# IQDemod.net
KiCad netlist of a schematic drawn in Altium Designer
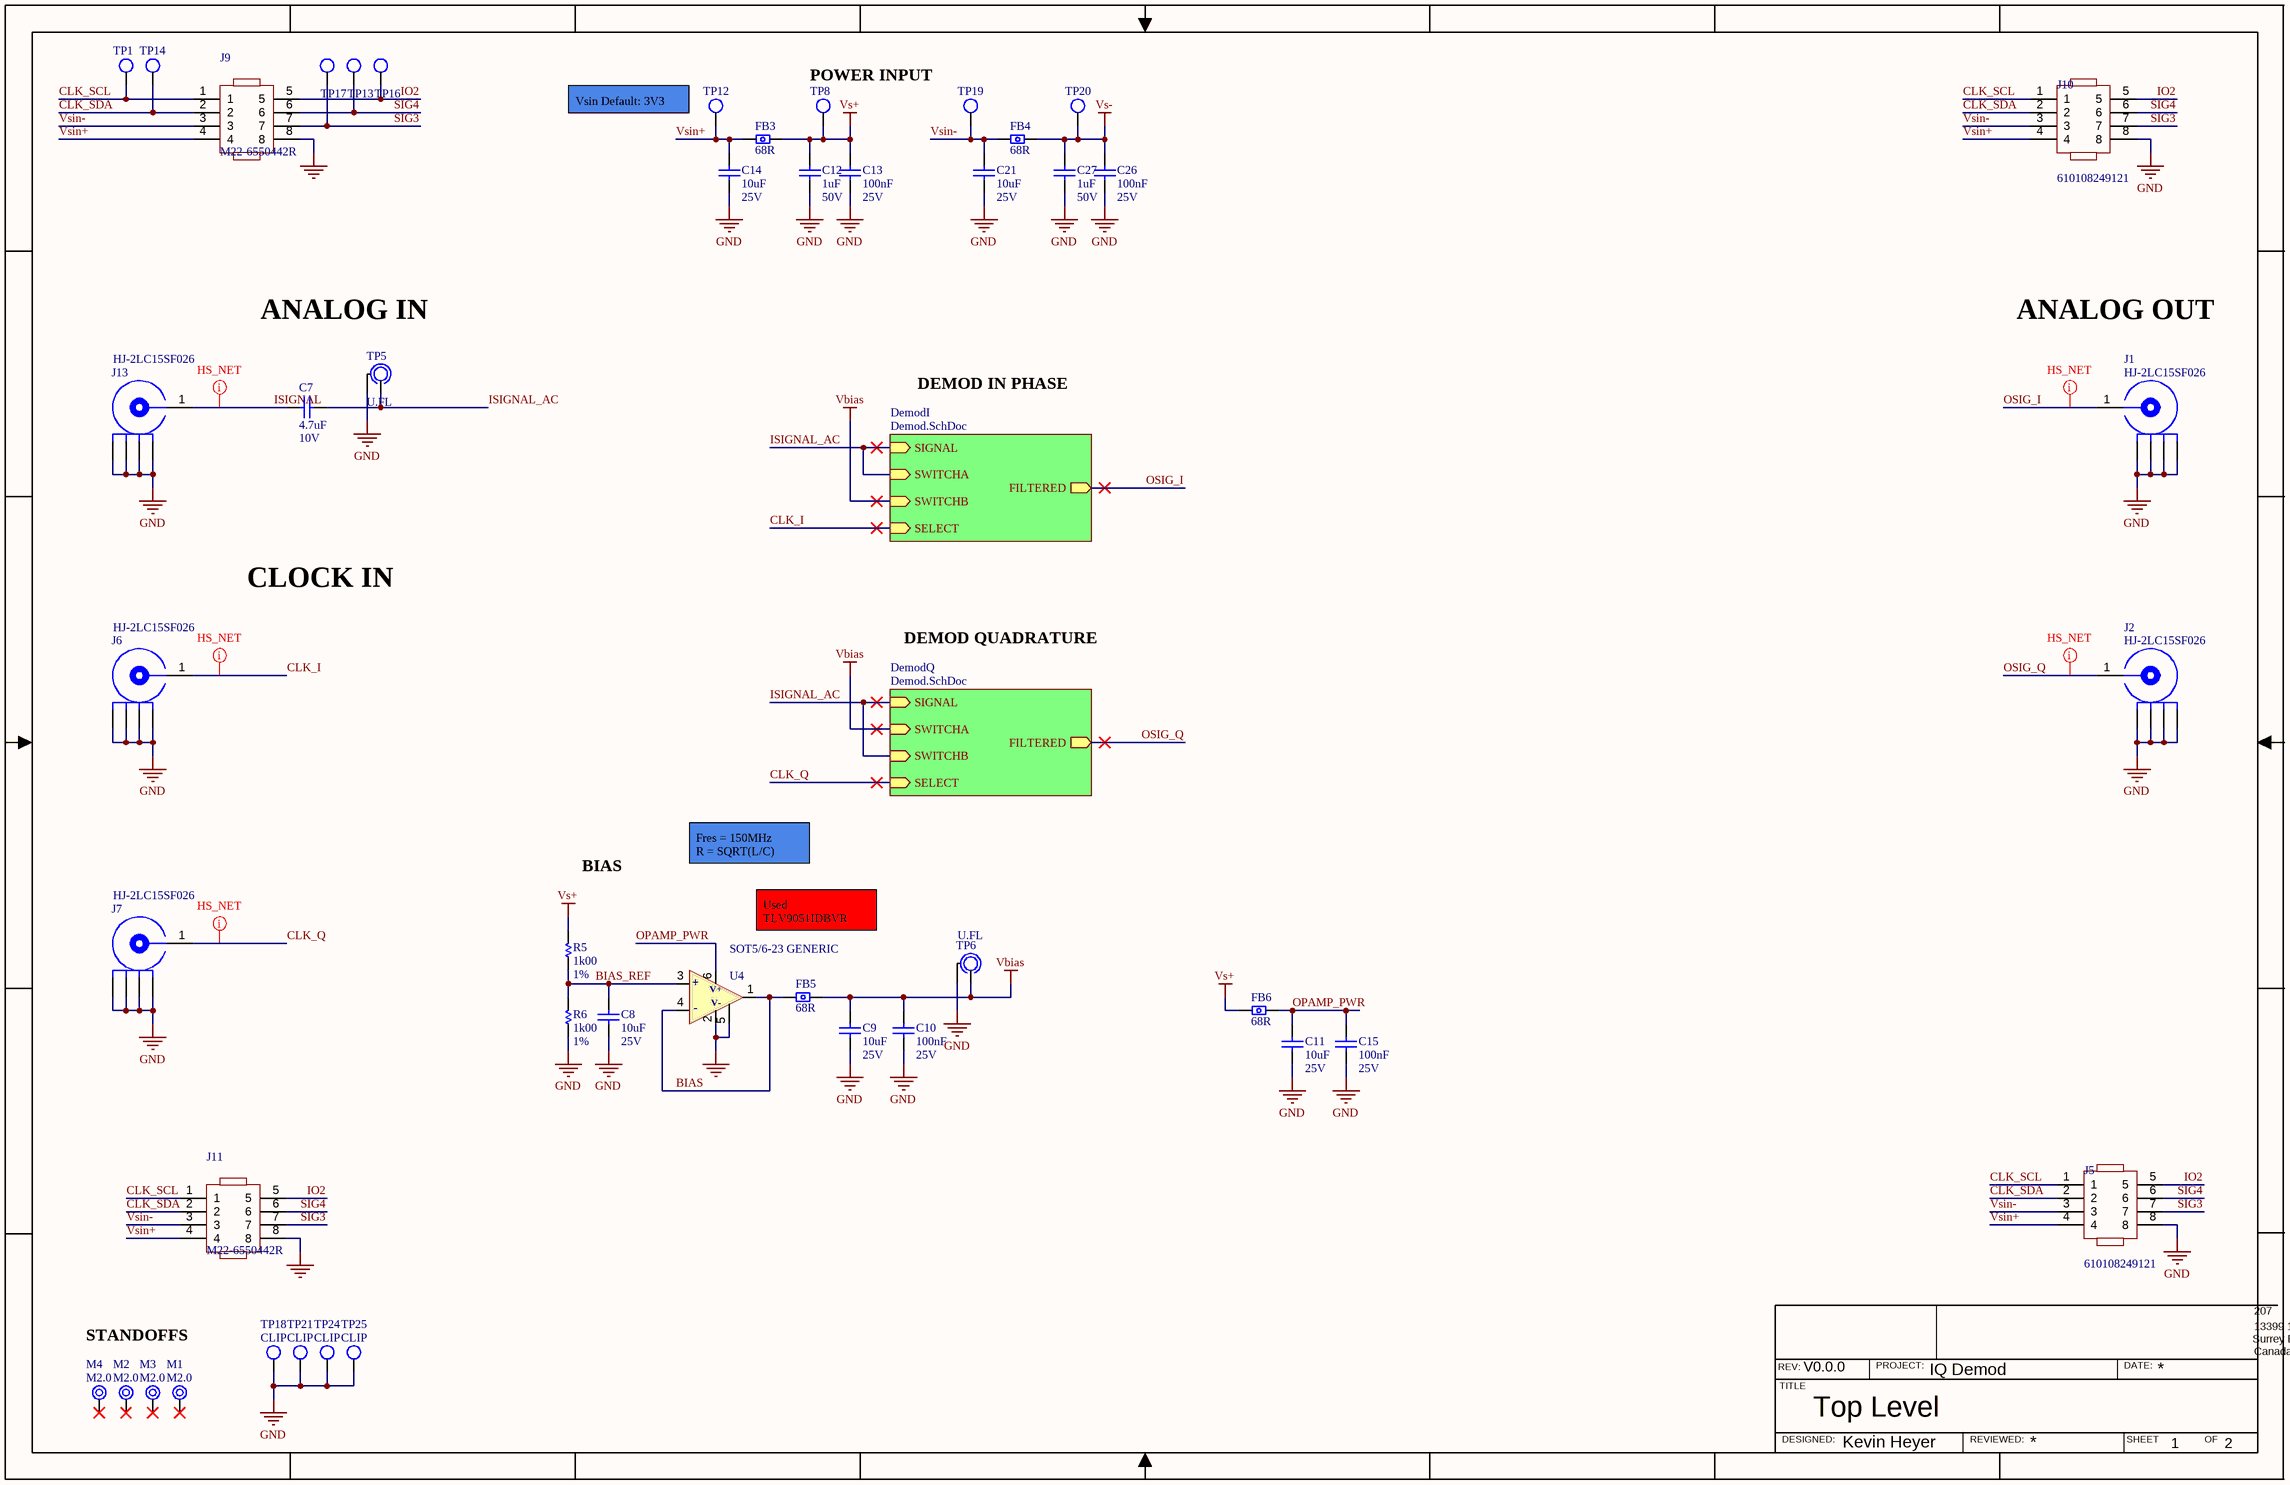
[diagram p0: IQDemod.SchDoc]

(export (version "E")
  (design (tool "Eeschema 10.0.6"))
  (components
    (comp (ref "C7")
      (value "4.7uF")
      (footprint "C0402")
      (description "0402 10 V 4.7 uF ±20% Tolerance X5R Multilayer Ceramic Chip Capacitor")
      (fields
        (field (name "MANUFACTURER") "Murata")
        (field (name "MANUFACTURER PART NUMBER") "GRM155R61A475MEAAD")
        (field (name "VOLTAGE RATING") "10V")
      )
      (libsource (lib "Symbols") (part "CAP CER 4.7uF 10V X5R 0402"))
    )
    (comp (ref "C8")
      (value "10uF")
      (footprint "c0805")
      (description "Cap Ceramic 10uF 25V X5R 10% SMD 0805 85°C Embossed T/R")
      (fields
        (field (name "MANUFACTURER") "Samsung")
        (field (name "MANUFACTURER PART NUMBER") "CL21A106KAYNNNE")
        (field (name "VOLTAGE RATING") "25V")
      )
      (libsource (lib "OPAMP_DEV_SOT5_6-23") (part "CAP CER 10uF 25V X5R 0805"))
    )
    (comp (ref "C9")
      (value "10uF")
      (footprint "c0805")
      (description "Cap Ceramic 10uF 25V X5R 10% SMD 0805 85°C Embossed T/R")
      (fields
        (field (name "MANUFACTURER") "Samsung")
        (field (name "MANUFACTURER PART NUMBER") "CL21A106KAYNNNE")
        (field (name "VOLTAGE RATING") "25V")
      )
      (libsource (lib "OPAMP_DEV_SOT5_6-23") (part "CAP CER 10uF 25V X5R 0805"))
    )
    (comp (ref "C10")
      (value "100nF")
      (footprint "C0402")
      (description "Cap Ceramic 0.1uF 25V X5R 10% Pad SMD 0402 85°C T/R / Multi Layer Ceramic Capacitor (MLCC)")
      (fields
        (field (name "MANUFACTURER") "Samsung")
        (field (name "MANUFACTURER PART NUMBER") "CL05A104KA5NNNC")
        (field (name "VOLTAGE RATING") "25V")
      )
      (libsource (lib "OPAMP_DEV_SOT5_6-23") (part "CAP CER 100nF 25V X5R 0402"))
    )
    (comp (ref "C11")
      (value "10uF")
      (footprint "c0805")
      (description "Cap Ceramic 10uF 25V X5R 10% SMD 0805 85°C Embossed T/R")
      (fields
        (field (name "MANUFACTURER") "Samsung")
        (field (name "MANUFACTURER PART NUMBER") "CL21A106KAYNNNE")
        (field (name "VOLTAGE RATING") "25V")
      )
      (libsource (lib "OPAMP_DEV_SOT5_6-23") (part "CAP CER 10uF 25V X5R 0805"))
    )
    (comp (ref "C12")
      (value "1uF")
      (footprint "c0603")
      (description "Multilayer Ceramic Capacitors (High dielectric type), 50V, 1 uF, ± 10 %, 0603, X5R, RoHS")
      (fields
        (field (name "MANUFACTURER") "Taiyo Yuden")
        (field (name "MANUFACTURER PART NUMBER") "UMK107BJ105KA-T")
        (field (name "VOLTAGE RATING") "50V")
      )
      (libsource (lib "OPAMP_DEV_SOT5_6-23") (part "CAP CER 1uF 50V X5R 0603"))
    )
    (comp (ref "C13")
      (value "100nF")
      (footprint "C0402")
      (description "Cap Ceramic 0.1uF 25V X5R 10% Pad SMD 0402 85°C T/R / Multi Layer Ceramic Capacitor (MLCC)")
      (fields
        (field (name "MANUFACTURER") "Samsung")
        (field (name "MANUFACTURER PART NUMBER") "CL05A104KA5NNNC")
        (field (name "VOLTAGE RATING") "25V")
      )
      (libsource (lib "OPAMP_DEV_SOT5_6-23") (part "CAP CER 100nF 25V X5R 0402"))
    )
    (comp (ref "C14")
      (value "10uF")
      (footprint "c0805")
      (description "Cap Ceramic 10uF 25V X5R 10% SMD 0805 85°C Embossed T/R")
      (fields
        (field (name "MANUFACTURER") "Samsung")
        (field (name "MANUFACTURER PART NUMBER") "CL21A106KAYNNNE")
        (field (name "VOLTAGE RATING") "25V")
      )
      (libsource (lib "OPAMP_DEV_SOT5_6-23") (part "CAP CER 10uF 25V X5R 0805"))
    )
    (comp (ref "C15")
      (value "100nF")
      (footprint "C0402")
      (description "Cap Ceramic 0.1uF 25V X5R 10% Pad SMD 0402 85°C T/R / Multi Layer Ceramic Capacitor (MLCC)")
      (fields
        (field (name "MANUFACTURER") "Samsung")
        (field (name "MANUFACTURER PART NUMBER") "CL05A104KA5NNNC")
        (field (name "VOLTAGE RATING") "25V")
      )
      (libsource (lib "OPAMP_DEV_SOT5_6-23") (part "CAP CER 100nF 25V X5R 0402"))
    )
    (comp (ref "C21")
      (value "10uF")
      (footprint "c0805")
      (description "Cap Ceramic 10uF 25V X5R 10% SMD 0805 85°C Embossed T/R")
      (fields
        (field (name "MANUFACTURER") "Samsung")
        (field (name "MANUFACTURER PART NUMBER") "CL21A106KAYNNNE")
        (field (name "VOLTAGE RATING") "25V")
      )
      (libsource (lib "OPAMP_DEV_SOT5_6-23") (part "CAP CER 10uF 25V X5R 0805"))
    )
    (comp (ref "C26")
      (value "100nF")
      (footprint "C0402")
      (description "Cap Ceramic 0.1uF 25V X5R 10% Pad SMD 0402 85°C T/R / Multi Layer Ceramic Capacitor (MLCC)")
      (fields
        (field (name "MANUFACTURER") "Samsung")
        (field (name "MANUFACTURER PART NUMBER") "CL05A104KA5NNNC")
        (field (name "VOLTAGE RATING") "25V")
      )
      (libsource (lib "OPAMP_DEV_SOT5_6-23") (part "CAP CER 100nF 25V X5R 0402"))
    )
    (comp (ref "C27")
      (value "1uF")
      (footprint "c0603")
      (description "Multilayer Ceramic Capacitors (High dielectric type), 50V, 1 uF, ± 10 %, 0603, X5R, RoHS")
      (fields
        (field (name "MANUFACTURER") "Taiyo Yuden")
        (field (name "MANUFACTURER PART NUMBER") "UMK107BJ105KA-T")
        (field (name "VOLTAGE RATING") "50V")
      )
      (libsource (lib "OPAMP_DEV_SOT5_6-23") (part "CAP CER 1uF 50V X5R 0603"))
    )
    (comp (ref "FB3")
      (value "68R")
      (footprint "FB0402")
      (description "Ferrite Beads Multi-Layer 68Ohm 25% 100MHz 400mA 310mOhm DCR 0402 T/R")
      (fields
        (field (name "MANUFACTURER") "Taiyo Yuden")
        (field (name "MANUFACTURER PART NUMBER") "BK1005LL680-T")
      )
      (libsource (lib "MCU") (part "FB 68R 400mA 310mR 0402"))
    )
    (comp (ref "FB4")
      (value "68R")
      (footprint "FB0402")
      (description "Ferrite Beads Multi-Layer 68Ohm 25% 100MHz 400mA 310mOhm DCR 0402 T/R")
      (fields
        (field (name "MANUFACTURER") "Taiyo Yuden")
        (field (name "MANUFACTURER PART NUMBER") "BK1005LL680-T")
      )
      (libsource (lib "MCU") (part "FB 68R 400mA 310mR 0402"))
    )
    (comp (ref "FB5")
      (value "68R")
      (footprint "FB0402")
      (description "Ferrite Beads Multi-Layer 68Ohm 25% 100MHz 400mA 310mOhm DCR 0402 T/R")
      (fields
        (field (name "MANUFACTURER") "Taiyo Yuden")
        (field (name "MANUFACTURER PART NUMBER") "BK1005LL680-T")
      )
      (libsource (lib "MCU") (part "FB 68R 400mA 310mR 0402"))
    )
    (comp (ref "FB6")
      (value "68R")
      (footprint "FB0402")
      (description "Ferrite Beads Multi-Layer 68Ohm 25% 100MHz 400mA 310mOhm DCR 0402 T/R")
      (fields
        (field (name "MANUFACTURER") "Taiyo Yuden")
        (field (name "MANUFACTURER PART NUMBER") "BK1005LL680-T")
      )
      (libsource (lib "MCU") (part "FB 68R 400mA 310mR 0402"))
    )
    (comp (ref "J1")
      (value "HJ-2LC15SF026")
      (footprint "SMA TH BORE")
      (libsource (lib "") (part "CON SMA BORE TH HJ-SMA058_1"))
    )
    (comp (ref "J2")
      (value "HJ-2LC15SF026")
      (footprint "SMA TH BORE")
      (libsource (lib "") (part "CON SMA BORE TH HJ-SMA058_1"))
    )
    (comp (ref "J5")
      (value "610108249121")
      (footprint "CONN HDR 08 MALE RA 2ROW - duplicate")
      (description "SMT Angled Pin Header WR-PHD, Pitch 2.54 mm, Dual Row, 8 pins")
      (fields (field (name "MANUFACTURER") "Wurth Electronics"))
      (libsource (lib "Symbols") (part "CONN HDR 08 MALE RA 2 ROW"))
    )
    (comp (ref "J6")
      (value "HJ-2LC15SF026")
      (footprint "SMA TH BORE")
      (libsource (lib "Symbols") (part "CON SMA BORE TH HJ-SMA058"))
    )
    (comp (ref "J7")
      (value "HJ-2LC15SF026")
      (footprint "SMA TH BORE")
      (libsource (lib "Symbols") (part "CON SMA BORE TH HJ-SMA058"))
    )
    (comp (ref "J9")
      (value "M22-6550442R")
      (footprint "CONN HDR 08 FEMALE RA 2ROW")
      (description "Conn Socket Strip RCP 8 POS 2mm Solder RA SMD T/R")
      (fields (field (name "MANUFACTURER") "Harwin"))
      (libsource (lib "Symbols") (part "CONN HDR 08 FEMALE RA 2 ROW"))
    )
    (comp (ref "J10")
      (value "610108249121")
      (footprint "CONN HDR 08 MALE RA 2ROW - duplicate")
      (description "SMT Angled Pin Header WR-PHD, Pitch 2.54 mm, Dual Row, 8 pins")
      (fields (field (name "MANUFACTURER") "Wurth Electronics"))
      (libsource (lib "Symbols") (part "CONN HDR 08 MALE RA 2 ROW"))
    )
    (comp (ref "J11")
      (value "M22-6550442R")
      (footprint "CONN HDR 08 FEMALE RA 2ROW")
      (description "Conn Socket Strip RCP 8 POS 2mm Solder RA SMD T/R")
      (fields (field (name "MANUFACTURER") "Harwin"))
      (libsource (lib "Symbols") (part "CONN HDR 08 FEMALE RA 2 ROW"))
    )
    (comp (ref "J13")
      (value "HJ-2LC15SF026")
      (footprint "SMA TH BORE")
      (libsource (lib "Symbols") (part "CON SMA BORE TH HJ-SMA058"))
    )
    (comp (ref "M1")
      (value "M2.0")
      (footprint "MECH M2.0 UNPLATED")
      (libsource (lib "OPAMP_DEV_SOT5_6-23") (part "MECH M2.0 UNPLATED"))
    )
    (comp (ref "M2")
      (value "M2.0")
      (footprint "MECH M2.0 UNPLATED")
      (libsource (lib "OPAMP_DEV_SOT5_6-23") (part "MECH M2.0 UNPLATED"))
    )
    (comp (ref "M3")
      (value "M2.0")
      (footprint "MECH M2.0 UNPLATED")
      (libsource (lib "OPAMP_DEV_SOT5_6-23") (part "MECH M2.0 UNPLATED"))
    )
    (comp (ref "M4")
      (value "M2.0")
      (footprint "MECH M2.0 UNPLATED")
      (libsource (lib "OPAMP_DEV_SOT5_6-23") (part "MECH M2.0 UNPLATED"))
    )
    (comp (ref "R5")
      (value "1k00")
      (footprint "R0402")
      (description "1 kOhms ±1% 0.063W, 1/16W Chip Resistor 0402 (1005 Metric) Moisture Resistant Thick Film")
      (fields
        (field (name "MANUFACTURER") "Yageo")
        (field (name "MANUFACTURER PART NUMBER") "RC0402FR-071KL")
        (field (name "TOLERANCE") "1%")
      )
      (libsource (lib "Symbols") (part "RES 1k00 63mW 0402"))
    )
    (comp (ref "R6")
      (value "1k00")
      (footprint "R0402")
      (description "1 kOhms ±1% 0.063W, 1/16W Chip Resistor 0402 (1005 Metric) Moisture Resistant Thick Film")
      (fields
        (field (name "MANUFACTURER") "Yageo")
        (field (name "MANUFACTURER PART NUMBER") "RC0402FR-071KL")
        (field (name "TOLERANCE") "1%")
      )
      (libsource (lib "Symbols") (part "RES 1k00 63mW 0402"))
    )
    (comp (ref "TP1")
      (value "1mm")
      (footprint "TESTPOINT_SMT")
      (description "SMT testpoint")
      (libsource (lib "OPAMP_DEV_SOT5_6-23") (part "TP 1mm"))
    )
    (comp (ref "TP5")
      (value "U.FL")
      (footprint "U.FL")
      (description "CONN U.FL RCPT STR 50 OHM SMD")
      (fields
        (field (name "MANUFACTURER") "Hirose")
        (field (name "MANUFACTURER PART NUMBER") "U.FL-R-SMT-1(80)")
      )
      (libsource (lib "OPAMP_DEV_SOT5_6-23") (part "TP U.FL"))
    )
    (comp (ref "TP6")
      (value "U.FL")
      (footprint "U.FL")
      (description "CONN U.FL RCPT STR 50 OHM SMD")
      (fields
        (field (name "MANUFACTURER") "Hirose")
        (field (name "MANUFACTURER PART NUMBER") "U.FL-R-SMT-1(80)")
      )
      (libsource (lib "OPAMP_DEV_SOT5_6-23") (part "TP U.FL"))
    )
    (comp (ref "TP8")
      (value "1mm")
      (footprint "TESTPOINT_SMT")
      (description "SMT testpoint")
      (libsource (lib "OPAMP_DEV_SOT5_6-23") (part "TP 1mm"))
    )
    (comp (ref "TP12")
      (value "1mm")
      (footprint "TESTPOINT_SMT")
      (description "SMT testpoint")
      (libsource (lib "OPAMP_DEV_SOT5_6-23") (part "TP 1mm"))
    )
    (comp (ref "TP13")
      (value "1mm")
      (footprint "TESTPOINT_SMT")
      (description "SMT testpoint")
      (libsource (lib "OPAMP_DEV_SOT5_6-23") (part "TP 1mm"))
    )
    (comp (ref "TP14")
      (value "1mm")
      (footprint "TESTPOINT_SMT")
      (description "SMT testpoint")
      (libsource (lib "OPAMP_DEV_SOT5_6-23") (part "TP 1mm"))
    )
    (comp (ref "TP16")
      (value "1mm")
      (footprint "TESTPOINT_SMT")
      (description "SMT testpoint")
      (libsource (lib "OPAMP_DEV_SOT5_6-23") (part "TP 1mm"))
    )
    (comp (ref "TP17")
      (value "1mm")
      (footprint "TESTPOINT_SMT")
      (description "SMT testpoint")
      (libsource (lib "OPAMP_DEV_SOT5_6-23") (part "TP 1mm"))
    )
    (comp (ref "TP18")
      (value "CLIP")
      (footprint "TESTPOINT_CLIP_1206")
      (description "Current Sense Resistors - SMD CHIP CHECKER HT=2.0 1206")
      (fields (field (name "MANUFACTURER") "KOA Speer") (field (name "MANUFACTURER PART NUMBER") "RCWCTE"))
      (libsource (lib "Symbols") (part "TP CLIP 1206 RCWCTE"))
    )
    (comp (ref "TP19")
      (value "1mm")
      (footprint "TESTPOINT_SMT")
      (description "SMT testpoint")
      (libsource (lib "OPAMP_DEV_SOT5_6-23") (part "TP 1mm"))
    )
    (comp (ref "TP20")
      (value "1mm")
      (footprint "TESTPOINT_SMT")
      (description "SMT testpoint")
      (libsource (lib "OPAMP_DEV_SOT5_6-23") (part "TP 1mm"))
    )
    (comp (ref "TP21")
      (value "CLIP")
      (footprint "TESTPOINT_CLIP_1206")
      (description "Current Sense Resistors - SMD CHIP CHECKER HT=2.0 1206")
      (fields (field (name "MANUFACTURER") "KOA Speer") (field (name "MANUFACTURER PART NUMBER") "RCWCTE"))
      (libsource (lib "Symbols") (part "TP CLIP 1206 RCWCTE"))
    )
    (comp (ref "TP24")
      (value "CLIP")
      (footprint "TESTPOINT_CLIP_1206")
      (description "Current Sense Resistors - SMD CHIP CHECKER HT=2.0 1206")
      (fields (field (name "MANUFACTURER") "KOA Speer") (field (name "MANUFACTURER PART NUMBER") "RCWCTE"))
      (libsource (lib "Symbols") (part "TP CLIP 1206 RCWCTE"))
    )
    (comp (ref "TP25")
      (value "CLIP")
      (footprint "TESTPOINT_CLIP_1206")
      (description "Current Sense Resistors - SMD CHIP CHECKER HT=2.0 1206")
      (fields (field (name "MANUFACTURER") "KOA Speer") (field (name "MANUFACTURER PART NUMBER") "RCWCTE"))
      (libsource (lib "Symbols") (part "TP CLIP 1206 RCWCTE"))
    )
    (comp (ref "U4")
      (value "SOT5/6-23 GENERIC")
      (footprint "SOT23-5/6_Modified")
      (libsource (lib "LaserDiode_Analog") (part "IC OPAMP SOT5/6-23 GENERIC"))
    )
  )
  (nets
    (net (code "1") (name "/BIAS") (class "Default")
      (node (ref "FB5") (pin "2") (pintype "passive"))
      (node (ref "U4") (pin "1") (pinfunction "1_1") (pintype "passive"))
      (node (ref "U4") (pin "4") (pinfunction "-_4") (pintype "passive"))
    )
    (net (code "2") (name "/BIAS_REF") (class "Default")
      (node (ref "C8") (pin "2") (pinfunction "2_2") (pintype "passive"))
      (node (ref "R5") (pin "1") (pinfunction "1_1") (pintype "passive"))
      (node (ref "R6") (pin "2") (pinfunction "2_2") (pintype "passive"))
      (node (ref "U4") (pin "3") (pinfunction "+_3") (pintype "passive"))
    )
    (net (code "3") (name "/CLK_I") (class "Default")
      (node (ref "J6") (pin "1") (pinfunction "1_1") (pintype "passive"))
    )
    (net (code "4") (name "/CLK_Q") (class "Default")
      (node (ref "J7") (pin "1") (pinfunction "1_1") (pintype "passive"))
    )
    (net (code "5") (name "/CLK_SCL") (class "Default")
      (node (ref "J10") (pin "1") (pinfunction "1_1") (pintype "passive"))
      (node (ref "J11") (pin "1") (pinfunction "1_1") (pintype "passive"))
      (node (ref "J5") (pin "1") (pinfunction "1_1") (pintype "passive"))
      (node (ref "J9") (pin "1") (pinfunction "1_1") (pintype "passive"))
      (node (ref "TP1") (pin "1") (pinfunction "1_1") (pintype "passive"))
    )
    (net (code "6") (name "/CLK_SDA") (class "Default")
      (node (ref "J10") (pin "2") (pinfunction "2_2") (pintype "passive"))
      (node (ref "J11") (pin "2") (pinfunction "2_2") (pintype "passive"))
      (node (ref "J5") (pin "2") (pinfunction "2_2") (pintype "passive"))
      (node (ref "J9") (pin "2") (pinfunction "2_2") (pintype "passive"))
      (node (ref "TP14") (pin "1") (pinfunction "1_1") (pintype "passive"))
    )
    (net (code "7") (name "/IO2") (class "Default")
      (node (ref "J10") (pin "5") (pinfunction "5_5") (pintype "passive"))
      (node (ref "J11") (pin "5") (pinfunction "5_5") (pintype "passive"))
      (node (ref "J5") (pin "5") (pinfunction "5_5") (pintype "passive"))
      (node (ref "J9") (pin "5") (pinfunction "5_5") (pintype "passive"))
      (node (ref "TP16") (pin "1") (pinfunction "1_1") (pintype "passive"))
    )
    (net (code "8") (name "/ISIGNAL") (class "Default")
      (node (ref "C7") (pin "1") (pinfunction "1_1") (pintype "passive"))
      (node (ref "J13") (pin "1") (pinfunction "1_1") (pintype "passive"))
    )
    (net (code "9") (name "/ISIGNAL_AC") (class "Default")
      (node (ref "C7") (pin "2") (pinfunction "2_2") (pintype "passive"))
      (node (ref "TP5") (pin "1") (pinfunction "1_1") (pintype "passive"))
    )
    (net (code "10") (name "/OPAMP_PWR") (class "Default")
      (node (ref "C11") (pin "2") (pinfunction "2_2") (pintype "passive"))
      (node (ref "C15") (pin "1") (pinfunction "1_1") (pintype "passive"))
      (node (ref "FB6") (pin "1") (pintype "passive"))
      (node (ref "U4") (pin "6") (pinfunction "V+_6") (pintype "passive"))
    )
    (net (code "11") (name "/OSIG_I") (class "Default")
      (node (ref "J1") (pin "1") (pinfunction "1_1") (pintype "passive"))
    )
    (net (code "12") (name "/OSIG_Q") (class "Default")
      (node (ref "J2") (pin "1") (pinfunction "1_1") (pintype "passive"))
    )
    (net (code "13") (name "/SIG3") (class "Default")
      (node (ref "J10") (pin "7") (pinfunction "7_7") (pintype "passive"))
      (node (ref "J11") (pin "7") (pinfunction "7_7") (pintype "passive"))
      (node (ref "J5") (pin "7") (pinfunction "7_7") (pintype "passive"))
      (node (ref "J9") (pin "7") (pinfunction "7_7") (pintype "passive"))
      (node (ref "TP17") (pin "1") (pinfunction "1_1") (pintype "passive"))
    )
    (net (code "14") (name "/SIG4") (class "Default")
      (node (ref "J10") (pin "6") (pinfunction "6_6") (pintype "passive"))
      (node (ref "J11") (pin "6") (pinfunction "6_6") (pintype "passive"))
      (node (ref "J5") (pin "6") (pinfunction "6_6") (pintype "passive"))
      (node (ref "J9") (pin "6") (pinfunction "6_6") (pintype "passive"))
      (node (ref "TP13") (pin "1") (pinfunction "1_1") (pintype "passive"))
    )
    (net (code "15") (name "/Vsin+") (class "Default")
      (node (ref "C14") (pin "2") (pinfunction "2_2") (pintype "passive"))
      (node (ref "FB3") (pin "2") (pintype "passive"))
      (node (ref "J10") (pin "4") (pinfunction "4_4") (pintype "passive"))
      (node (ref "J11") (pin "4") (pinfunction "4_4") (pintype "passive"))
      (node (ref "J5") (pin "4") (pinfunction "4_4") (pintype "passive"))
      (node (ref "J9") (pin "4") (pinfunction "4_4") (pintype "passive"))
      (node (ref "TP12") (pin "1") (pinfunction "1_1") (pintype "passive"))
    )
    (net (code "16") (name "/Vsin-") (class "Default")
      (node (ref "C21") (pin "2") (pinfunction "2_2") (pintype "passive"))
      (node (ref "FB4") (pin "2") (pintype "passive"))
      (node (ref "J10") (pin "3") (pinfunction "3_3") (pintype "passive"))
      (node (ref "J11") (pin "3") (pinfunction "3_3") (pintype "passive"))
      (node (ref "J5") (pin "3") (pinfunction "3_3") (pintype "passive"))
      (node (ref "J9") (pin "3") (pinfunction "3_3") (pintype "passive"))
      (node (ref "TP19") (pin "1") (pinfunction "1_1") (pintype "passive"))
    )
    (net (code "17") (name "GND") (class "Default")
      (node (ref "C10") (pin "2") (pinfunction "2_2") (pintype "passive"))
      (node (ref "C11") (pin "1") (pinfunction "1_1") (pintype "passive"))
      (node (ref "C12") (pin "1") (pinfunction "1_1") (pintype "passive"))
      (node (ref "C13") (pin "1") (pinfunction "1_1") (pintype "passive"))
      (node (ref "C14") (pin "1") (pinfunction "1_1") (pintype "passive"))
      (node (ref "C15") (pin "2") (pinfunction "2_2") (pintype "passive"))
      (node (ref "C21") (pin "1") (pinfunction "1_1") (pintype "passive"))
      (node (ref "C26") (pin "1") (pinfunction "1_1") (pintype "passive"))
      (node (ref "C27") (pin "1") (pinfunction "1_1") (pintype "passive"))
      (node (ref "C8") (pin "1") (pinfunction "1_1") (pintype "passive"))
      (node (ref "C9") (pin "1") (pinfunction "1_1") (pintype "passive"))
      (node (ref "J1") (pin "0") (pinfunction "5_0") (pintype "passive"))
      (node (ref "J10") (pin "8") (pinfunction "8_8") (pintype "passive"))
      (node (ref "J11") (pin "8") (pinfunction "8_8") (pintype "passive"))
      (node (ref "J13") (pin "0") (pinfunction "5_0") (pintype "passive"))
      (node (ref "J2") (pin "0") (pinfunction "4_0") (pintype "passive"))
      (node (ref "J5") (pin "8") (pinfunction "8_8") (pintype "passive"))
      (node (ref "J6") (pin "0") (pinfunction "2_0") (pintype "passive"))
      (node (ref "J7") (pin "0") (pinfunction "4_0") (pintype "passive"))
      (node (ref "J9") (pin "8") (pinfunction "8_8") (pintype "passive"))
      (node (ref "R6") (pin "1") (pinfunction "1_1") (pintype "passive"))
      (node (ref "TP18") (pin "1") (pinfunction "1_1") (pintype "passive"))
      (node (ref "TP21") (pin "1") (pinfunction "1_1") (pintype "passive"))
      (node (ref "TP24") (pin "1") (pinfunction "1_1") (pintype "passive"))
      (node (ref "TP25") (pin "1") (pinfunction "1_1") (pintype "passive"))
      (node (ref "TP5") (pin "0") (pinfunction "0_0") (pintype "passive"))
      (node (ref "TP6") (pin "0") (pinfunction "0_0") (pintype "passive"))
      (node (ref "U4") (pin "2") (pinfunction "V-_2") (pintype "passive"))
      (node (ref "U4") (pin "5") (pinfunction "1_5") (pintype "passive"))
    )
    (net (code "18") (name "Vbias") (class "Default")
      (node (ref "C10") (pin "1") (pinfunction "1_1") (pintype "passive"))
      (node (ref "C9") (pin "2") (pinfunction "2_2") (pintype "passive"))
      (node (ref "FB5") (pin "1") (pintype "passive"))
      (node (ref "TP6") (pin "1") (pinfunction "1_1") (pintype "passive"))
    )
    (net (code "19") (name "Vs+") (class "Default")
      (node (ref "C12") (pin "2") (pinfunction "2_2") (pintype "passive"))
      (node (ref "C13") (pin "2") (pinfunction "2_2") (pintype "passive"))
      (node (ref "FB3") (pin "1") (pintype "passive"))
      (node (ref "FB6") (pin "2") (pintype "passive"))
      (node (ref "R5") (pin "2") (pinfunction "2_2") (pintype "passive"))
      (node (ref "TP8") (pin "1") (pinfunction "1_1") (pintype "passive"))
    )
    (net (code "20") (name "Vs-") (class "Default")
      (node (ref "C26") (pin "2") (pinfunction "2_2") (pintype "passive"))
      (node (ref "C27") (pin "2") (pinfunction "2_2") (pintype "passive"))
      (node (ref "FB4") (pin "1") (pintype "passive"))
      (node (ref "TP20") (pin "1") (pinfunction "1_1") (pintype "passive"))
    )
    (net (code "21") (name "unconnected-(M1-Pad1)") (class "Default")
      (node (ref "M1") (pin "1") (pinfunction "1_1") (pintype "passive+no_connect"))
    )
    (net (code "22") (name "unconnected-(M2-Pad1)") (class "Default")
      (node (ref "M2") (pin "1") (pinfunction "1_1") (pintype "passive+no_connect"))
    )
    (net (code "23") (name "unconnected-(M3-Pad1)") (class "Default")
      (node (ref "M3") (pin "1") (pinfunction "1_1") (pintype "passive+no_connect"))
    )
    (net (code "24") (name "unconnected-(M4-Pad1)") (class "Default")
      (node (ref "M4") (pin "1") (pinfunction "1_1") (pintype "passive+no_connect"))
    )
  )
)
